# IRComms.net
KiCad netlist of a schematic drawn in Altium Designer
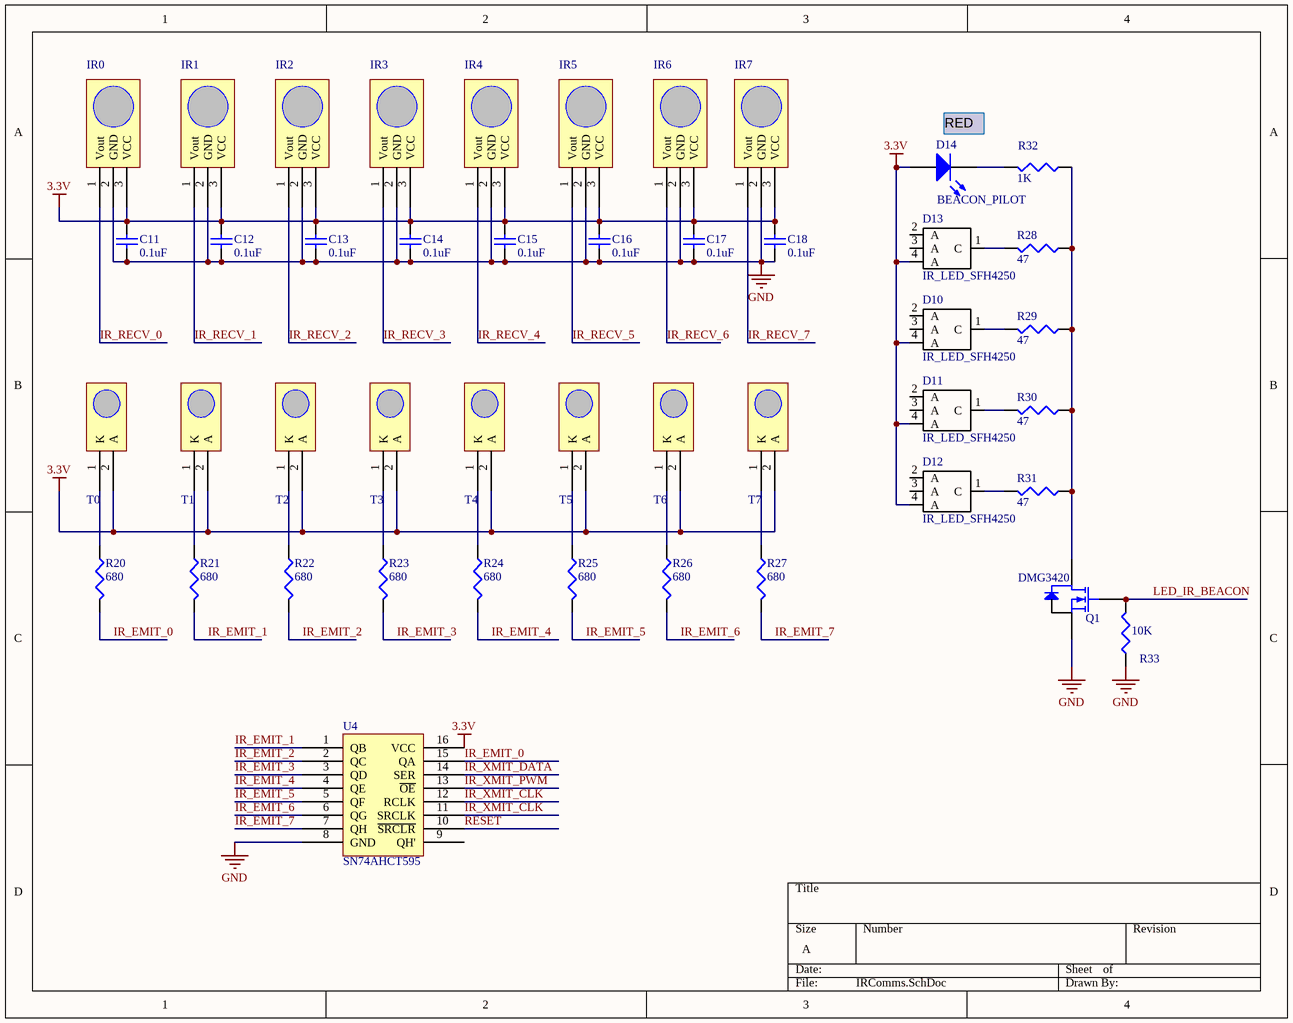
[diagram p0: IRComms.SchDoc]

(export (version "E")
  (design (tool "Eeschema 10.0.6"))
  (components
    (comp (ref "C11")
      (value "0.1uF")
      (footprint "CAPC1005L")
      (description "Capacitor (Semiconductor SIM Model)")
      (fields (field (name "Comment") "Cap Semi") (field (name "PUBLISHER") "Altium Limited"))
      (libsource (lib "Miscellaneous Devices") (part "Cap Semi"))
    )
    (comp (ref "C12")
      (value "0.1uF")
      (footprint "CAPC1005L")
      (description "Capacitor (Semiconductor SIM Model)")
      (fields (field (name "Comment") "Cap Semi") (field (name "PUBLISHER") "Altium Limited"))
      (libsource (lib "Miscellaneous Devices") (part "Cap Semi"))
    )
    (comp (ref "C13")
      (value "0.1uF")
      (footprint "CAPC1005L")
      (description "Capacitor (Semiconductor SIM Model)")
      (fields (field (name "Comment") "Cap Semi") (field (name "PUBLISHER") "Altium Limited"))
      (libsource (lib "Miscellaneous Devices") (part "Cap Semi"))
    )
    (comp (ref "C14")
      (value "0.1uF")
      (footprint "CAPC1005L")
      (description "Capacitor (Semiconductor SIM Model)")
      (fields (field (name "Comment") "Cap Semi") (field (name "PUBLISHER") "Altium Limited"))
      (libsource (lib "Miscellaneous Devices") (part "Cap Semi"))
    )
    (comp (ref "C15")
      (value "0.1uF")
      (footprint "CAPC1005L")
      (description "Capacitor (Semiconductor SIM Model)")
      (fields (field (name "Comment") "Cap Semi") (field (name "PUBLISHER") "Altium Limited"))
      (libsource (lib "Miscellaneous Devices") (part "Cap Semi"))
    )
    (comp (ref "C16")
      (value "0.1uF")
      (footprint "CAPC1005L")
      (description "Capacitor (Semiconductor SIM Model)")
      (fields (field (name "Comment") "Cap Semi") (field (name "PUBLISHER") "Altium Limited"))
      (libsource (lib "Miscellaneous Devices") (part "Cap Semi"))
    )
    (comp (ref "C17")
      (value "0.1uF")
      (footprint "CAPC1005L")
      (description "Capacitor (Semiconductor SIM Model)")
      (fields (field (name "Comment") "Cap Semi") (field (name "PUBLISHER") "Altium Limited"))
      (libsource (lib "Miscellaneous Devices") (part "Cap Semi"))
    )
    (comp (ref "C18")
      (value "0.1uF")
      (footprint "CAPC1005L")
      (description "Capacitor (Semiconductor SIM Model)")
      (fields (field (name "Comment") "Cap Semi") (field (name "PUBLISHER") "Altium Limited"))
      (libsource (lib "Miscellaneous Devices") (part "Cap Semi"))
    )
    (comp (ref "D10")
      (value "IR_LED_SFH4250")
      (footprint "IR_LED_SFH4250")
      (libsource (lib "mrone") (part "IR_LED_SFH4250"))
    )
    (comp (ref "D11")
      (value "IR_LED_SFH4250")
      (footprint "IR_LED_SFH4250")
      (libsource (lib "mrone") (part "IR_LED_SFH4250"))
    )
    (comp (ref "D12")
      (value "IR_LED_SFH4250")
      (footprint "IR_LED_SFH4250")
      (libsource (lib "mrone") (part "IR_LED_SFH4250"))
    )
    (comp (ref "D13")
      (value "IR_LED_SFH4250")
      (footprint "IR_LED_SFH4250")
      (libsource (lib "mrone") (part "IR_LED_SFH4250"))
    )
    (comp (ref "D14")
      (value "BEACON_PILOT")
      (footprint "SurfaceMount(603)")
      (libsource (lib "mrone") (part "LED"))
    )
    (comp (ref "IR0")
      (value "GP1UX31QS")
      (footprint "GP1UX31QS")
      (libsource (lib "mrone") (part "GP1UX31QS"))
    )
    (comp (ref "IR1")
      (value "GP1UX31QS")
      (footprint "GP1UX31QS")
      (libsource (lib "mrone") (part "GP1UX31QS"))
    )
    (comp (ref "IR2")
      (value "GP1UX31QS")
      (footprint "GP1UX31QS")
      (libsource (lib "mrone") (part "GP1UX31QS"))
    )
    (comp (ref "IR3")
      (value "GP1UX31QS")
      (footprint "GP1UX31QS")
      (libsource (lib "mrone") (part "GP1UX31QS"))
    )
    (comp (ref "IR4")
      (value "GP1UX31QS")
      (footprint "GP1UX31QS")
      (libsource (lib "mrone") (part "GP1UX31QS"))
    )
    (comp (ref "IR5")
      (value "GP1UX31QS")
      (footprint "GP1UX31QS")
      (libsource (lib "mrone") (part "GP1UX31QS"))
    )
    (comp (ref "IR6")
      (value "GP1UX31QS")
      (footprint "GP1UX31QS")
      (libsource (lib "mrone") (part "GP1UX31QS"))
    )
    (comp (ref "IR7")
      (value "GP1UX31QS")
      (footprint "GP1UX31QS")
      (libsource (lib "mrone") (part "GP1UX31QS"))
    )
    (comp (ref "Q1")
      (value "Mosfet")
      (footprint "SOT-23")
      (fields (field (name "MPN") "DMG3420"))
      (libsource (lib "mrone") (part "Mosfet"))
    )
    (comp (ref "R20")
      (value "680")
      (footprint "RESC1608L")
      (description "Resistor")
      (fields (field (name "Comment") "Res3") (field (name "PUBLISHER") "Altium Limited"))
      (libsource (lib "Miscellaneous Devices") (part "Res3"))
    )
    (comp (ref "R21")
      (value "680")
      (footprint "RESC1608L")
      (description "Resistor")
      (fields (field (name "Comment") "Res3") (field (name "PUBLISHER") "Altium Limited"))
      (libsource (lib "Miscellaneous Devices") (part "Res3"))
    )
    (comp (ref "R22")
      (value "680")
      (footprint "RESC1608L")
      (description "Resistor")
      (fields (field (name "Comment") "Res3") (field (name "PUBLISHER") "Altium Limited"))
      (libsource (lib "Miscellaneous Devices") (part "Res3"))
    )
    (comp (ref "R23")
      (value "680")
      (footprint "RESC1608L")
      (description "Resistor")
      (fields (field (name "Comment") "Res3") (field (name "PUBLISHER") "Altium Limited"))
      (libsource (lib "Miscellaneous Devices") (part "Res3"))
    )
    (comp (ref "R24")
      (value "680")
      (footprint "RESC1608L")
      (description "Resistor")
      (fields (field (name "Comment") "Res3") (field (name "PUBLISHER") "Altium Limited"))
      (libsource (lib "Miscellaneous Devices") (part "Res3"))
    )
    (comp (ref "R25")
      (value "680")
      (footprint "RESC1608L")
      (description "Resistor")
      (fields (field (name "Comment") "Res3") (field (name "PUBLISHER") "Altium Limited"))
      (libsource (lib "Miscellaneous Devices") (part "Res3"))
    )
    (comp (ref "R26")
      (value "680")
      (footprint "RESC1608L")
      (description "Resistor")
      (fields (field (name "Comment") "Res3") (field (name "PUBLISHER") "Altium Limited"))
      (libsource (lib "Miscellaneous Devices") (part "Res3"))
    )
    (comp (ref "R27")
      (value "680")
      (footprint "RESC1608L")
      (description "Resistor")
      (fields (field (name "Comment") "Res3") (field (name "PUBLISHER") "Altium Limited"))
      (libsource (lib "Miscellaneous Devices") (part "Res3"))
    )
    (comp (ref "R28")
      (value "47")
      (footprint "RESC1608L")
      (description "Resistor")
      (fields (field (name "Comment") "Res3") (field (name "PUBLISHER") "Altium Limited"))
      (libsource (lib "Miscellaneous Devices") (part "Res3"))
    )
    (comp (ref "R29")
      (value "47")
      (footprint "RESC1608L")
      (description "Resistor")
      (fields (field (name "Comment") "Res3") (field (name "PUBLISHER") "Altium Limited"))
      (libsource (lib "Miscellaneous Devices") (part "Res3"))
    )
    (comp (ref "R30")
      (value "47")
      (footprint "RESC1608L")
      (description "Resistor")
      (fields (field (name "Comment") "Res3") (field (name "PUBLISHER") "Altium Limited"))
      (libsource (lib "Miscellaneous Devices") (part "Res3"))
    )
    (comp (ref "R31")
      (value "47")
      (footprint "RESC1608L")
      (description "Resistor")
      (fields (field (name "Comment") "Res3") (field (name "PUBLISHER") "Altium Limited"))
      (libsource (lib "Miscellaneous Devices") (part "Res3"))
    )
    (comp (ref "R32")
      (value "1K")
      (footprint "RESC1608L")
      (description "Resistor")
      (fields (field (name "Comment") "Res3") (field (name "PUBLISHER") "Altium Limited"))
      (libsource (lib "Miscellaneous Devices") (part "Res3"))
    )
    (comp (ref "R33")
      (value "10K")
      (footprint "RESC1608L")
      (description "Resistor")
      (fields (field (name "Comment") "Res3") (field (name "PUBLISHER") "Altium Limited"))
      (libsource (lib "Miscellaneous Devices") (part "Res3"))
    )
    (comp (ref "T0") (value "LN54") (footprint "LN54") (libsource (lib "mrone") (part "LN54")))
    (comp (ref "T1") (value "LN54") (footprint "LN54") (libsource (lib "mrone") (part "LN54")))
    (comp (ref "T2") (value "LN54") (footprint "LN54") (libsource (lib "mrone") (part "LN54")))
    (comp (ref "T3") (value "LN54") (footprint "LN54") (libsource (lib "mrone") (part "LN54")))
    (comp (ref "T4") (value "LN54") (footprint "LN54") (libsource (lib "mrone") (part "LN54")))
    (comp (ref "T5") (value "LN54") (footprint "LN54") (libsource (lib "mrone") (part "LN54")))
    (comp (ref "T6") (value "LN54") (footprint "LN54") (libsource (lib "mrone") (part "LN54")))
    (comp (ref "T7") (value "LN54") (footprint "LN54") (libsource (lib "mrone") (part "LN54")))
    (comp (ref "U4")
      (value "SN74AHCT595")
      (footprint "TSSOP-16")
      (description "shift register")
      (libsource (lib "mrone") (part "SN74AHCT595"))
    )
  )
  (nets
    (net (code "1") (name "/IR_EMIT_0") (class "Default")
      (node (ref "R20") (pin "2") (pinfunction "2_2") (pintype "passive"))
      (node (ref "U4") (pin "15") (pinfunction "QA_15") (pintype "passive"))
    )
    (net (code "2") (name "/IR_EMIT_1") (class "Default")
      (node (ref "R21") (pin "2") (pinfunction "2_2") (pintype "passive"))
      (node (ref "U4") (pin "1") (pinfunction "QB_1") (pintype "passive"))
    )
    (net (code "3") (name "/IR_EMIT_2") (class "Default")
      (node (ref "R22") (pin "2") (pinfunction "2_2") (pintype "passive"))
      (node (ref "U4") (pin "2") (pinfunction "QC_2") (pintype "passive"))
    )
    (net (code "4") (name "/IR_EMIT_3") (class "Default")
      (node (ref "R23") (pin "2") (pinfunction "2_2") (pintype "passive"))
      (node (ref "U4") (pin "3") (pinfunction "QD_3") (pintype "passive"))
    )
    (net (code "5") (name "/IR_EMIT_4") (class "Default")
      (node (ref "R24") (pin "2") (pinfunction "2_2") (pintype "passive"))
      (node (ref "U4") (pin "4") (pinfunction "QE_4") (pintype "passive"))
    )
    (net (code "6") (name "/IR_EMIT_5") (class "Default")
      (node (ref "R25") (pin "2") (pinfunction "2_2") (pintype "passive"))
      (node (ref "U4") (pin "5") (pinfunction "QF_5") (pintype "passive"))
    )
    (net (code "7") (name "/IR_EMIT_6") (class "Default")
      (node (ref "R26") (pin "2") (pinfunction "2_2") (pintype "passive"))
      (node (ref "U4") (pin "6") (pinfunction "QG_6") (pintype "passive"))
    )
    (net (code "8") (name "/IR_EMIT_7") (class "Default")
      (node (ref "R27") (pin "2") (pinfunction "2_2") (pintype "passive"))
      (node (ref "U4") (pin "7") (pinfunction "QH_7") (pintype "passive"))
    )
    (net (code "9") (name "/IR_RECV_0") (class "Default")
      (node (ref "IR0") (pin "1") (pinfunction "Vout_1") (pintype "passive"))
    )
    (net (code "10") (name "/IR_RECV_1") (class "Default")
      (node (ref "IR1") (pin "1") (pinfunction "Vout_1") (pintype "passive"))
    )
    (net (code "11") (name "/IR_RECV_2") (class "Default")
      (node (ref "IR2") (pin "1") (pinfunction "Vout_1") (pintype "passive"))
    )
    (net (code "12") (name "/IR_RECV_3") (class "Default")
      (node (ref "IR3") (pin "1") (pinfunction "Vout_1") (pintype "passive"))
    )
    (net (code "13") (name "/IR_RECV_4") (class "Default")
      (node (ref "IR4") (pin "1") (pinfunction "Vout_1") (pintype "passive"))
    )
    (net (code "14") (name "/IR_RECV_5") (class "Default")
      (node (ref "IR5") (pin "1") (pinfunction "Vout_1") (pintype "passive"))
    )
    (net (code "15") (name "/IR_RECV_6") (class "Default")
      (node (ref "IR6") (pin "1") (pinfunction "Vout_1") (pintype "passive"))
    )
    (net (code "16") (name "/IR_RECV_7") (class "Default")
      (node (ref "IR7") (pin "1") (pinfunction "Vout_1") (pintype "passive"))
    )
    (net (code "17") (name "/IR_XMIT_CLK") (class "Default")
      (node (ref "U4") (pin "11") (pinfunction "SRCLK_11") (pintype "passive"))
      (node (ref "U4") (pin "12") (pinfunction "RCLK_12") (pintype "passive"))
    )
    (net (code "18") (name "/IR_XMIT_DATA") (class "Default")
      (node (ref "U4") (pin "14") (pinfunction "SER_14") (pintype "passive"))
    )
    (net (code "19") (name "/IR_XMIT_PWM") (class "Default")
      (node (ref "U4") (pin "13") (pinfunction "~{OE}_13") (pintype "passive"))
    )
    (net (code "20") (name "/LED_IR_BEACON") (class "Default")
      (node (ref "Q1") (pin "1") (pinfunction "G_1") (pintype "passive"))
      (node (ref "R33") (pin "2") (pinfunction "2_2") (pintype "passive"))
    )
    (net (code "21") (name "/RESET") (class "Default")
      (node (ref "U4") (pin "10") (pinfunction "~{SRCLR}_10") (pintype "passive"))
    )
    (net (code "22") (name "3.3V") (class "Default")
      (node (ref "C11") (pin "2") (pinfunction "2_2") (pintype "passive"))
      (node (ref "C12") (pin "2") (pinfunction "2_2") (pintype "passive"))
      (node (ref "C13") (pin "2") (pinfunction "2_2") (pintype "passive"))
      (node (ref "C14") (pin "2") (pinfunction "2_2") (pintype "passive"))
      (node (ref "C15") (pin "2") (pinfunction "2_2") (pintype "passive"))
      (node (ref "C16") (pin "2") (pinfunction "2_2") (pintype "passive"))
      (node (ref "C17") (pin "2") (pinfunction "2_2") (pintype "passive"))
      (node (ref "C18") (pin "2") (pinfunction "2_2") (pintype "passive"))
      (node (ref "D10") (pin "4") (pinfunction "A_4") (pintype "passive"))
      (node (ref "D11") (pin "4") (pinfunction "A_4") (pintype "passive"))
      (node (ref "D12") (pin "4") (pinfunction "A_4") (pintype "passive"))
      (node (ref "D13") (pin "4") (pinfunction "A_4") (pintype "passive"))
      (node (ref "D14") (pin "1") (pinfunction "A_1") (pintype "passive"))
      (node (ref "IR0") (pin "3") (pinfunction "VCC_3") (pintype "power_in"))
      (node (ref "IR1") (pin "3") (pinfunction "VCC_3") (pintype "power_in"))
      (node (ref "IR2") (pin "3") (pinfunction "VCC_3") (pintype "power_in"))
      (node (ref "IR3") (pin "3") (pinfunction "VCC_3") (pintype "power_in"))
      (node (ref "IR4") (pin "3") (pinfunction "VCC_3") (pintype "power_in"))
      (node (ref "IR5") (pin "3") (pinfunction "VCC_3") (pintype "power_in"))
      (node (ref "IR6") (pin "3") (pinfunction "VCC_3") (pintype "power_in"))
      (node (ref "IR7") (pin "3") (pinfunction "VCC_3") (pintype "power_in"))
      (node (ref "T0") (pin "2") (pinfunction "A_2") (pintype "passive"))
      (node (ref "T1") (pin "2") (pinfunction "A_2") (pintype "passive"))
      (node (ref "T2") (pin "2") (pinfunction "A_2") (pintype "passive"))
      (node (ref "T3") (pin "2") (pinfunction "A_2") (pintype "passive"))
      (node (ref "T4") (pin "2") (pinfunction "A_2") (pintype "passive"))
      (node (ref "T5") (pin "2") (pinfunction "A_2") (pintype "passive"))
      (node (ref "T6") (pin "2") (pinfunction "A_2") (pintype "passive"))
      (node (ref "T7") (pin "2") (pinfunction "A_2") (pintype "passive"))
      (node (ref "U4") (pin "16") (pinfunction "VCC_16") (pintype "passive"))
    )
    (net (code "23") (name "GND") (class "Default")
      (node (ref "C11") (pin "1") (pinfunction "1_1") (pintype "passive"))
      (node (ref "C12") (pin "1") (pinfunction "1_1") (pintype "passive"))
      (node (ref "C13") (pin "1") (pinfunction "1_1") (pintype "passive"))
      (node (ref "C14") (pin "1") (pinfunction "1_1") (pintype "passive"))
      (node (ref "C15") (pin "1") (pinfunction "1_1") (pintype "passive"))
      (node (ref "C16") (pin "1") (pinfunction "1_1") (pintype "passive"))
      (node (ref "C17") (pin "1") (pinfunction "1_1") (pintype "passive"))
      (node (ref "C18") (pin "1") (pinfunction "1_1") (pintype "passive"))
      (node (ref "IR0") (pin "2") (pinfunction "GND_2") (pintype "power_in"))
      (node (ref "IR1") (pin "2") (pinfunction "GND_2") (pintype "power_in"))
      (node (ref "IR2") (pin "2") (pinfunction "GND_2") (pintype "power_in"))
      (node (ref "IR3") (pin "2") (pinfunction "GND_2") (pintype "power_in"))
      (node (ref "IR4") (pin "2") (pinfunction "GND_2") (pintype "power_in"))
      (node (ref "IR5") (pin "2") (pinfunction "GND_2") (pintype "power_in"))
      (node (ref "IR6") (pin "2") (pinfunction "GND_2") (pintype "power_in"))
      (node (ref "IR7") (pin "2") (pinfunction "GND_2") (pintype "power_in"))
      (node (ref "Q1") (pin "2") (pinfunction "S_2") (pintype "passive"))
      (node (ref "R33") (pin "1") (pinfunction "1_1") (pintype "passive"))
      (node (ref "U4") (pin "8") (pinfunction "GND_8") (pintype "passive"))
    )
    (net (code "24") (name "Net-(D10-C)") (class "Default")
      (node (ref "D10") (pin "1") (pinfunction "C_1") (pintype "passive"))
      (node (ref "R29") (pin "2") (pinfunction "2_2") (pintype "passive"))
    )
    (net (code "25") (name "Net-(D11-C)") (class "Default")
      (node (ref "D11") (pin "1") (pinfunction "C_1") (pintype "passive"))
      (node (ref "R30") (pin "2") (pinfunction "2_2") (pintype "passive"))
    )
    (net (code "26") (name "Net-(D12-C)") (class "Default")
      (node (ref "D12") (pin "1") (pinfunction "C_1") (pintype "passive"))
      (node (ref "R31") (pin "2") (pinfunction "2_2") (pintype "passive"))
    )
    (net (code "27") (name "Net-(D13-C)") (class "Default")
      (node (ref "D13") (pin "1") (pinfunction "C_1") (pintype "passive"))
      (node (ref "R28") (pin "2") (pinfunction "2_2") (pintype "passive"))
    )
    (net (code "28") (name "Net-(D14-K)") (class "Default")
      (node (ref "D14") (pin "2") (pinfunction "K_2") (pintype "passive"))
      (node (ref "R32") (pin "2") (pinfunction "2_2") (pintype "passive"))
    )
    (net (code "29") (name "Net-(Q1-D)") (class "Default")
      (node (ref "Q1") (pin "3") (pinfunction "D_3") (pintype "passive"))
      (node (ref "R28") (pin "1") (pinfunction "1_1") (pintype "passive"))
      (node (ref "R29") (pin "1") (pinfunction "1_1") (pintype "passive"))
      (node (ref "R30") (pin "1") (pinfunction "1_1") (pintype "passive"))
      (node (ref "R31") (pin "1") (pinfunction "1_1") (pintype "passive"))
      (node (ref "R32") (pin "1") (pinfunction "1_1") (pintype "passive"))
    )
    (net (code "30") (name "Net-(T0-K)") (class "Default")
      (node (ref "R20") (pin "1") (pinfunction "1_1") (pintype "passive"))
      (node (ref "T0") (pin "1") (pinfunction "K_1") (pintype "passive"))
    )
    (net (code "31") (name "Net-(T1-K)") (class "Default")
      (node (ref "R21") (pin "1") (pinfunction "1_1") (pintype "passive"))
      (node (ref "T1") (pin "1") (pinfunction "K_1") (pintype "passive"))
    )
    (net (code "32") (name "Net-(T2-K)") (class "Default")
      (node (ref "R22") (pin "1") (pinfunction "1_1") (pintype "passive"))
      (node (ref "T2") (pin "1") (pinfunction "K_1") (pintype "passive"))
    )
    (net (code "33") (name "Net-(T3-K)") (class "Default")
      (node (ref "R23") (pin "1") (pinfunction "1_1") (pintype "passive"))
      (node (ref "T3") (pin "1") (pinfunction "K_1") (pintype "passive"))
    )
    (net (code "34") (name "Net-(T4-K)") (class "Default")
      (node (ref "R24") (pin "1") (pinfunction "1_1") (pintype "passive"))
      (node (ref "T4") (pin "1") (pinfunction "K_1") (pintype "passive"))
    )
    (net (code "35") (name "Net-(T5-K)") (class "Default")
      (node (ref "R25") (pin "1") (pinfunction "1_1") (pintype "passive"))
      (node (ref "T5") (pin "1") (pinfunction "K_1") (pintype "passive"))
    )
    (net (code "36") (name "Net-(T6-K)") (class "Default")
      (node (ref "R26") (pin "1") (pinfunction "1_1") (pintype "passive"))
      (node (ref "T6") (pin "1") (pinfunction "K_1") (pintype "passive"))
    )
    (net (code "37") (name "Net-(T7-K)") (class "Default")
      (node (ref "R27") (pin "1") (pinfunction "1_1") (pintype "passive"))
      (node (ref "T7") (pin "1") (pinfunction "K_1") (pintype "passive"))
    )
    (net (code "38") (name "unconnected-(D10-A-Pad2)") (class "Default")
      (node (ref "D10") (pin "2") (pinfunction "A_2") (pintype "passive"))
    )
    (net (code "39") (name "unconnected-(D10-A-Pad3)") (class "Default")
      (node (ref "D10") (pin "3") (pinfunction "A_3") (pintype "passive"))
    )
    (net (code "40") (name "unconnected-(D11-A-Pad2)") (class "Default")
      (node (ref "D11") (pin "2") (pinfunction "A_2") (pintype "passive"))
    )
    (net (code "41") (name "unconnected-(D11-A-Pad3)") (class "Default")
      (node (ref "D11") (pin "3") (pinfunction "A_3") (pintype "passive"))
    )
    (net (code "42") (name "unconnected-(D12-A-Pad2)") (class "Default")
      (node (ref "D12") (pin "2") (pinfunction "A_2") (pintype "passive"))
    )
    (net (code "43") (name "unconnected-(D12-A-Pad3)") (class "Default")
      (node (ref "D12") (pin "3") (pinfunction "A_3") (pintype "passive"))
    )
    (net (code "44") (name "unconnected-(D13-A-Pad2)") (class "Default")
      (node (ref "D13") (pin "2") (pinfunction "A_2") (pintype "passive"))
    )
    (net (code "45") (name "unconnected-(D13-A-Pad3)") (class "Default")
      (node (ref "D13") (pin "3") (pinfunction "A_3") (pintype "passive"))
    )
    (net (code "46") (name "unconnected-(U4-QH'-Pad9)") (class "Default")
      (node (ref "U4") (pin "9") (pinfunction "QH'_9") (pintype "passive"))
    )
  )
)
